# Precharge.net
KiCad netlist of a schematic drawn in Altium Designer
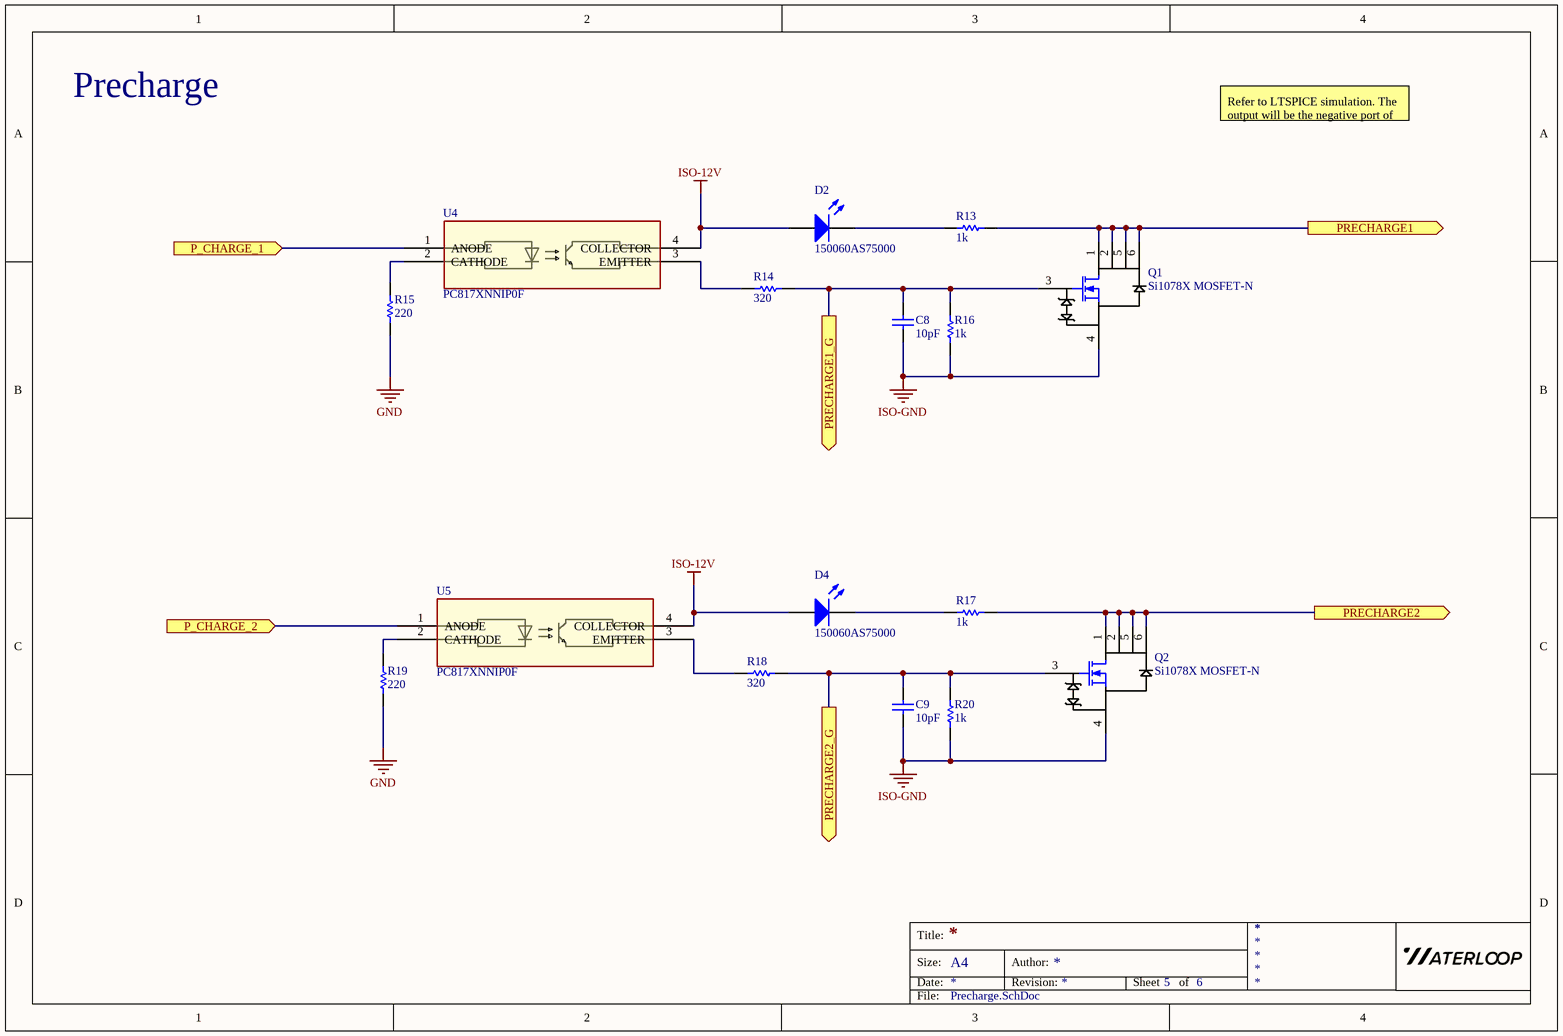
[diagram p0: Precharge.SchDoc]

(export (version "E")
  (design (tool "Eeschema 10.0.6"))
  (components
    (comp (ref "C8")
      (value "10pF")
      (footprint "0603 - Capacitor")
      (description "Nonpolarized Capacitor")
      (fields (field (name "Comment") "Capacitor - Nonpolarized"))
      (libsource (lib "General") (part "Capacitor - Nonpolarized"))
    )
    (comp (ref "C9")
      (value "10pF")
      (footprint "0603 - Capacitor")
      (description "Nonpolarized Capacitor")
      (fields (field (name "Comment") "Capacitor - Nonpolarized"))
      (libsource (lib "General") (part "Capacitor - Nonpolarized"))
    )
    (comp (ref "D2")
      (value "150060AS75000")
      (footprint "0603 - Resistor")
      (description "Amber 605nm LED Indication - Discrete 2V 0603 (1608 Metric)")
      (fields (field (name "MANUFACTURER") "Würth Elektronik"))
      (libsource (lib "General") (part "LED"))
    )
    (comp (ref "D4")
      (value "150060AS75000")
      (footprint "0603 - Resistor")
      (description "Amber 605nm LED Indication - Discrete 2V 0603 (1608 Metric)")
      (fields (field (name "MANUFACTURER") "Würth Elektronik"))
      (libsource (lib "General") (part "LED"))
    )
    (comp (ref "Q1")
      (value "Si1078X MOSFET-N")
      (footprint "Si1078X NMOS 30V")
      (description "N-Channel 30 V (D-S) MOSFET")
      (fields (field (name "MANUFACTURER PART NUMBER") "SI1078X-T1-GE3"))
      (libsource (lib "General") (part "Si1078X MOSFET-N"))
    )
    (comp (ref "Q2")
      (value "Si1078X MOSFET-N")
      (footprint "Si1078X NMOS 30V")
      (description "N-Channel 30 V (D-S) MOSFET")
      (fields (field (name "MANUFACTURER PART NUMBER") "SI1078X-T1-GE3"))
      (libsource (lib "General") (part "Si1078X MOSFET-N"))
    )
    (comp (ref "R13")
      (value "1k")
      (footprint "0603 - Resistor")
      (description "Resistor")
      (libsource (lib "General") (part "Resistor"))
    )
    (comp (ref "R14")
      (value "320")
      (footprint "0603 - Resistor")
      (description "Resistor")
      (libsource (lib "General") (part "Resistor"))
    )
    (comp (ref "R15")
      (value "220")
      (footprint "0603 - Resistor")
      (description "Resistor")
      (libsource (lib "General") (part "Resistor"))
    )
    (comp (ref "R16")
      (value "1k")
      (footprint "0603 - Resistor")
      (description "Resistor")
      (libsource (lib "General") (part "Resistor"))
    )
    (comp (ref "R17")
      (value "1k")
      (footprint "0603 - Resistor")
      (description "Resistor")
      (libsource (lib "General") (part "Resistor"))
    )
    (comp (ref "R18")
      (value "320")
      (footprint "0603 - Resistor")
      (description "Resistor")
      (libsource (lib "General") (part "Resistor"))
    )
    (comp (ref "R19")
      (value "220")
      (footprint "0603 - Resistor")
      (description "Resistor")
      (libsource (lib "General") (part "Resistor"))
    )
    (comp (ref "R20")
      (value "1k")
      (footprint "0603 - Resistor")
      (description "Resistor")
      (libsource (lib "General") (part "Resistor"))
    )
    (comp (ref "U4")
      (value "PC817XNNIP0F")
      (footprint "PC817XNNIP0F_SHP")
      (description "Transistor Output Optocouplers Photocoupler")
      (libsource (lib "BMS") (part "PC817XNNIP0F"))
    )
    (comp (ref "U5")
      (value "PC817XNNIP0F")
      (footprint "PC817XNNIP0F_SHP")
      (description "Transistor Output Optocouplers Photocoupler")
      (libsource (lib "BMS") (part "PC817XNNIP0F"))
    )
  )
  (nets
    (net (code "1") (name "/PRECHARGE1") (class "Default")
      (node (ref "Q1") (pin "1") (pinfunction "G_1") (pintype "passive"))
      (node (ref "Q1") (pin "2") (pinfunction "D_2") (pintype "passive"))
      (node (ref "Q1") (pin "5") (pinfunction "5_5") (pintype "passive"))
      (node (ref "Q1") (pin "6") (pinfunction "6_6") (pintype "passive"))
      (node (ref "R13") (pin "1") (pinfunction "1_1") (pintype "passive"))
    )
    (net (code "2") (name "/PRECHARGE1_G") (class "Default")
      (node (ref "C8") (pin "2") (pinfunction "2_2") (pintype "passive"))
      (node (ref "Q1") (pin "3") (pinfunction "3_3") (pintype "passive"))
      (node (ref "R14") (pin "2") (pinfunction "2_2") (pintype "passive"))
      (node (ref "R16") (pin "2") (pinfunction "2_2") (pintype "passive"))
    )
    (net (code "3") (name "/PRECHARGE2") (class "Default")
      (node (ref "Q2") (pin "1") (pinfunction "G_1") (pintype "passive"))
      (node (ref "Q2") (pin "2") (pinfunction "D_2") (pintype "passive"))
      (node (ref "Q2") (pin "5") (pinfunction "5_5") (pintype "passive"))
      (node (ref "Q2") (pin "6") (pinfunction "6_6") (pintype "passive"))
      (node (ref "R17") (pin "1") (pinfunction "1_1") (pintype "passive"))
    )
    (net (code "4") (name "/PRECHARGE2_G") (class "Default")
      (node (ref "C9") (pin "2") (pinfunction "2_2") (pintype "passive"))
      (node (ref "Q2") (pin "3") (pinfunction "3_3") (pintype "passive"))
      (node (ref "R18") (pin "2") (pinfunction "2_2") (pintype "passive"))
      (node (ref "R20") (pin "2") (pinfunction "2_2") (pintype "passive"))
    )
    (net (code "5") (name "/P_CHARGE_1") (class "Default")
      (node (ref "U4") (pin "1") (pinfunction "ANODE_1") (pintype "passive"))
    )
    (net (code "6") (name "/P_CHARGE_2") (class "Default")
      (node (ref "U5") (pin "1") (pinfunction "ANODE_1") (pintype "passive"))
    )
    (net (code "7") (name "GND") (class "Default")
      (node (ref "R15") (pin "1") (pinfunction "1_1") (pintype "passive"))
      (node (ref "R19") (pin "1") (pinfunction "1_1") (pintype "passive"))
    )
    (net (code "8") (name "ISO-12V") (class "Default")
      (node (ref "D2") (pin "1") (pinfunction "A_1") (pintype "passive"))
      (node (ref "D4") (pin "1") (pinfunction "A_1") (pintype "passive"))
      (node (ref "U4") (pin "4") (pinfunction "COLLECTOR_4") (pintype "passive"))
      (node (ref "U5") (pin "4") (pinfunction "COLLECTOR_4") (pintype "passive"))
    )
    (net (code "9") (name "ISO-GND") (class "Default")
      (node (ref "C8") (pin "1") (pinfunction "1_1") (pintype "passive"))
      (node (ref "C9") (pin "1") (pinfunction "1_1") (pintype "passive"))
      (node (ref "Q1") (pin "4") (pinfunction "4_4") (pintype "passive"))
      (node (ref "Q2") (pin "4") (pinfunction "4_4") (pintype "passive"))
      (node (ref "R16") (pin "1") (pinfunction "1_1") (pintype "passive"))
      (node (ref "R20") (pin "1") (pinfunction "1_1") (pintype "passive"))
    )
    (net (code "10") (name "Net-(D2-K)") (class "Default")
      (node (ref "D2") (pin "2") (pinfunction "K_2") (pintype "passive"))
      (node (ref "R13") (pin "2") (pinfunction "2_2") (pintype "passive"))
    )
    (net (code "11") (name "Net-(D4-K)") (class "Default")
      (node (ref "D4") (pin "2") (pinfunction "K_2") (pintype "passive"))
      (node (ref "R17") (pin "2") (pinfunction "2_2") (pintype "passive"))
    )
    (net (code "12") (name "Net-(U4-CATHODE)") (class "Default")
      (node (ref "R15") (pin "2") (pinfunction "2_2") (pintype "passive"))
      (node (ref "U4") (pin "2") (pinfunction "CATHODE_2") (pintype "passive"))
    )
    (net (code "13") (name "Net-(U4-EMITTER)") (class "Default")
      (node (ref "R14") (pin "1") (pinfunction "1_1") (pintype "passive"))
      (node (ref "U4") (pin "3") (pinfunction "EMITTER_3") (pintype "passive"))
    )
    (net (code "14") (name "Net-(U5-CATHODE)") (class "Default")
      (node (ref "R19") (pin "2") (pinfunction "2_2") (pintype "passive"))
      (node (ref "U5") (pin "2") (pinfunction "CATHODE_2") (pintype "passive"))
    )
    (net (code "15") (name "Net-(U5-EMITTER)") (class "Default")
      (node (ref "R18") (pin "1") (pinfunction "1_1") (pintype "passive"))
      (node (ref "U5") (pin "3") (pinfunction "EMITTER_3") (pintype "passive"))
    )
  )
)
